# Mega328MLF_Programmer.net
KiCad netlist of a schematic drawn in EAGLE
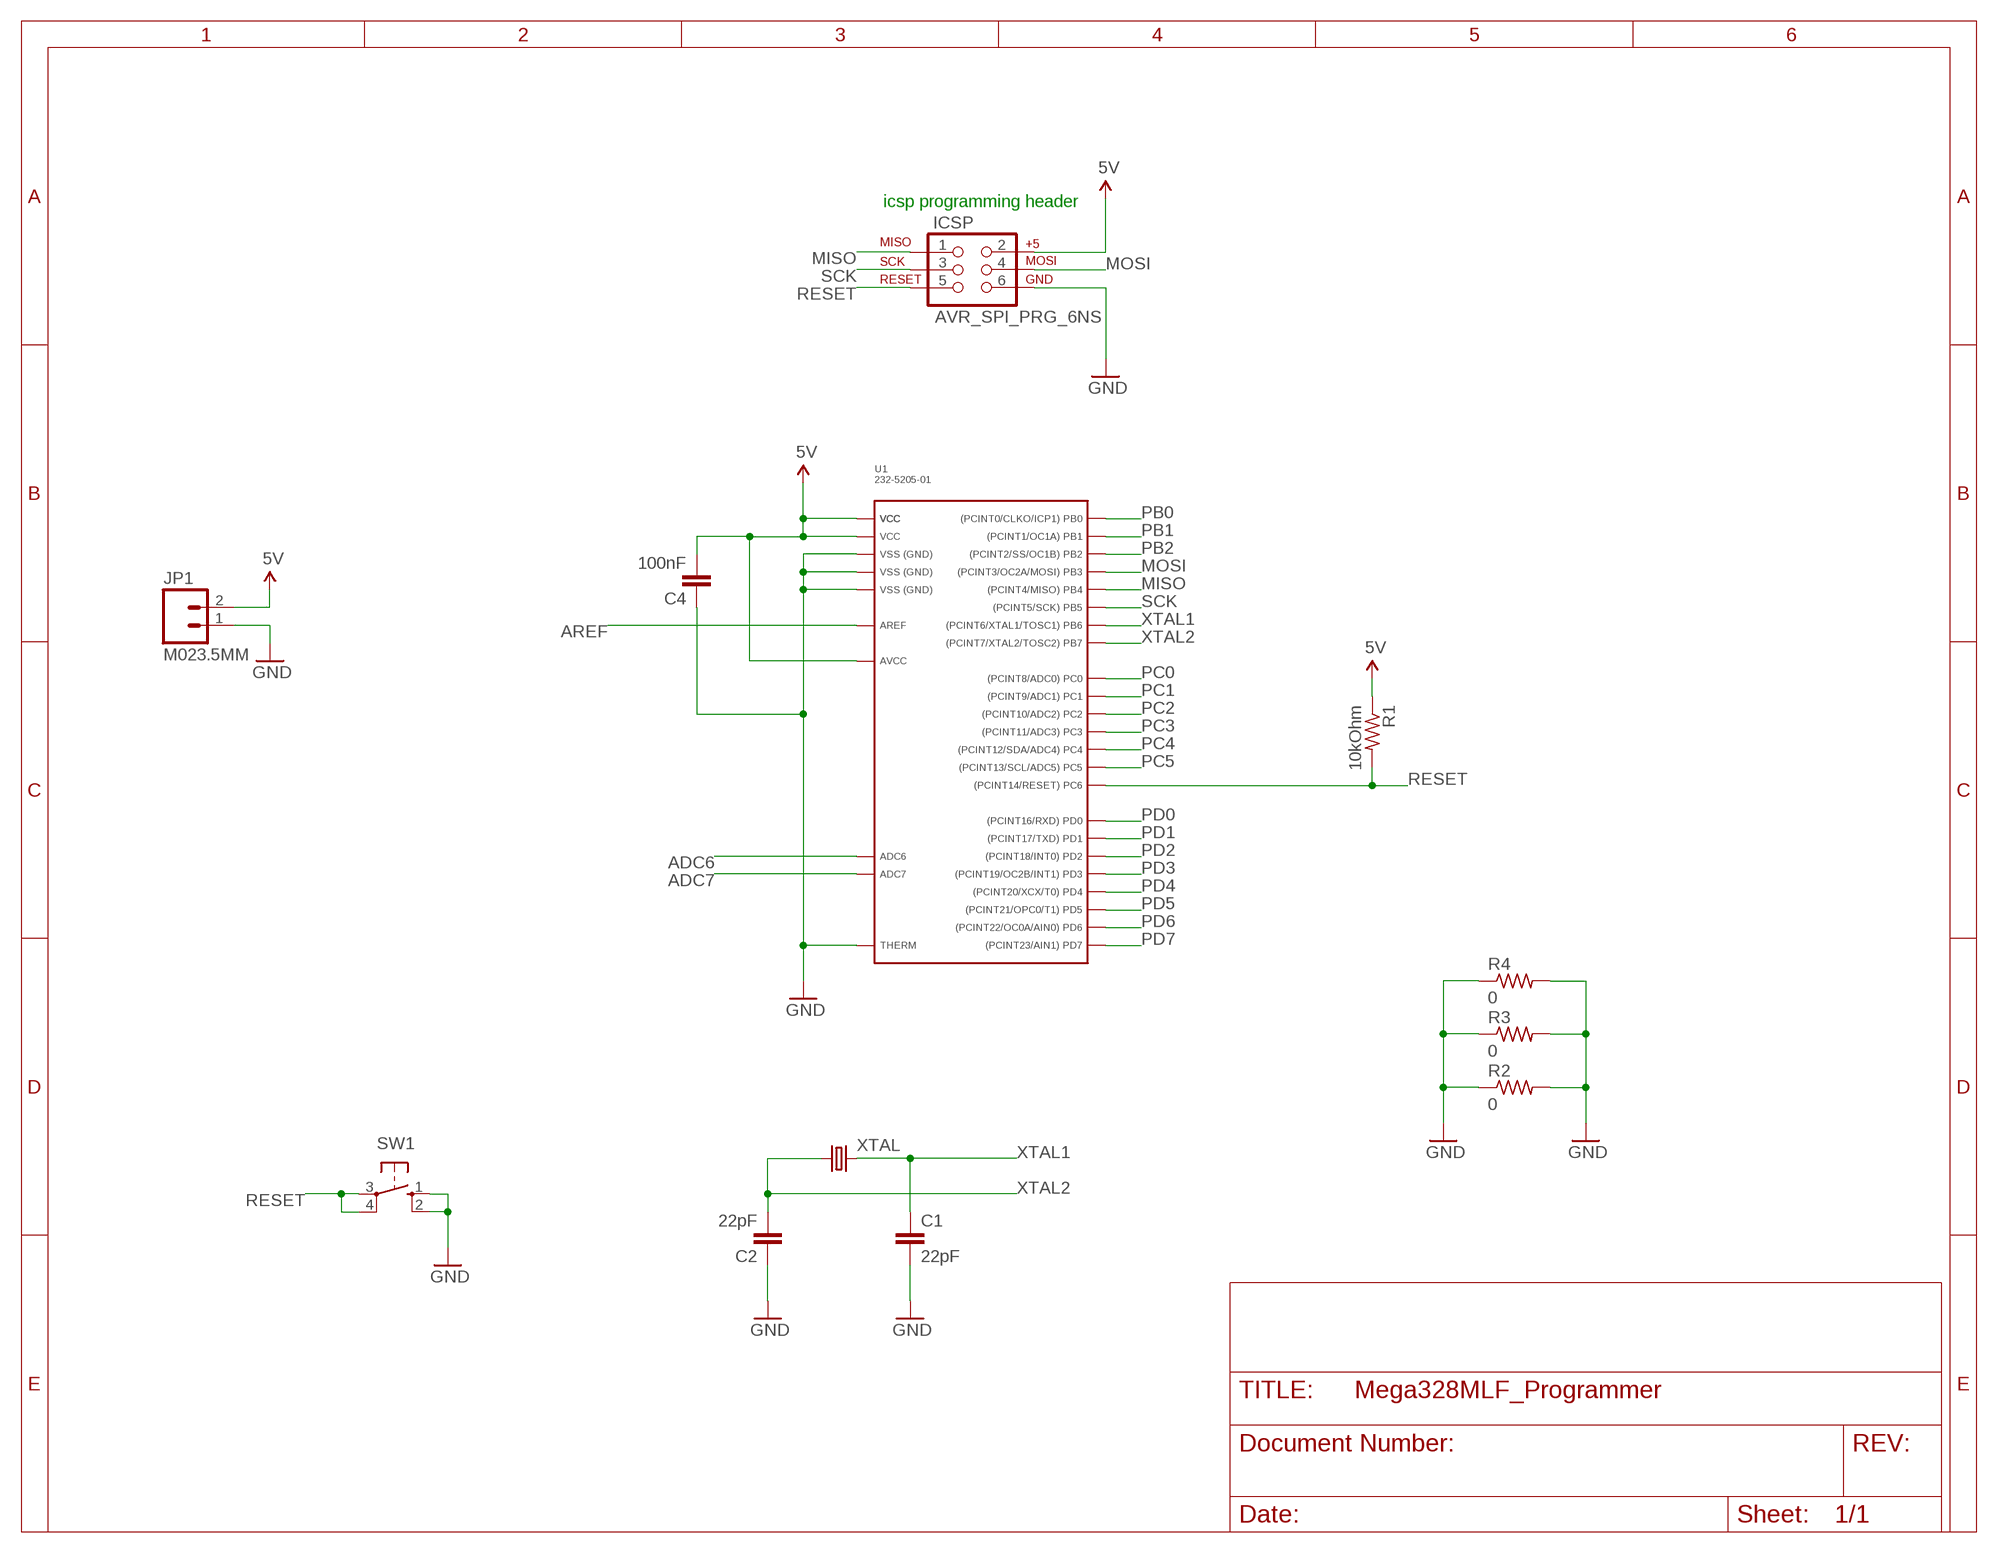
[diagram p0: schematic, sheet 1]

(export (version "E")
  (design (tool "Eeschema 10.0.6"))
  (components
    (comp (ref "C1")
      (value "22pF")
      (footprint "eagle-import:CAP-PTH-SMALL2")
      (libsource (lib "eagle-import") (part "CAPPTH2"))
    )
    (comp (ref "C2")
      (value "22pF")
      (footprint "eagle-import:CAP-PTH-SMALL2")
      (libsource (lib "eagle-import") (part "CAPPTH2"))
    )
    (comp (ref "C4")
      (value "100nF")
      (footprint "eagle-import:CAP-PTH-SMALL2")
      (libsource (lib "eagle-import") (part "CAPPTH2"))
    )
    (comp (ref "ICSP")
      (value "AVR_SPI_PRG_6NS")
      (footprint "eagle-import:2X3-NS")
      (libsource (lib "eagle-import") (part "AVR_SPI_PRG_6NS"))
    )
    (comp (ref "JP1")
      (value "M023.5MM")
      (footprint "eagle-import:SCREWTERMINAL-3.5MM-2")
      (libsource (lib "eagle-import") (part "M023.5MM"))
    )
    (comp (ref "R1")
      (value "10kOhm")
      (footprint "eagle-import:0204_7")
      (libsource (lib "eagle-import") (part "R-US_0204/7"))
    )
    (comp (ref "R2")
      (value "0")
      (footprint "eagle-import:0204_7")
      (libsource (lib "eagle-import") (part "R-US_0204/7"))
    )
    (comp (ref "R3")
      (value "0")
      (footprint "eagle-import:0204_7")
      (libsource (lib "eagle-import") (part "R-US_0204/7"))
    )
    (comp (ref "R4")
      (value "0")
      (footprint "eagle-import:0204_7")
      (libsource (lib "eagle-import") (part "R-US_0204/7"))
    )
    (comp (ref "SW1")
      (value "10-XX")
      (footprint "eagle-import:B3F-10XX")
      (libsource (lib "eagle-import") (part "10-XX"))
    )
    (comp (ref "U1")
      (value "232-5205-01")
      (footprint "eagle-import:232-5205-01")
      (libsource (lib "eagle-import") (part "232-5205-01"))
    )
    (comp (ref "XTAL")
      (value "CRYSTALHC49UV")
      (footprint "eagle-import:HC49U-V")
      (libsource (lib "eagle-import") (part "CRYSTALHC49UV"))
    )
  )
  (nets
    (net (code "1") (name "5V") (class "Default")
      (node (ref "C4") (pin "2") (pinfunction "2_2") (pintype "passive"))
      (node (ref "ICSP") (pin "2") (pinfunction "2_2") (pintype "passive"))
      (node (ref "JP1") (pin "2") (pinfunction "2_2") (pintype "passive"))
      (node (ref "R1") (pin "1") (pinfunction "1_1") (pintype "passive"))
      (node (ref "U1") (pin "18") (pinfunction "AVCC_18") (pintype "power_in"))
      (node (ref "U1") (pin "4") (pinfunction "VCC_4") (pintype "power_in"))
      (node (ref "U1") (pin "6") (pinfunction "VCC_6") (pintype "power_in"))
    )
    (net (code "2") (name "ADC6") (class "Default")
      (node (ref "U1") (pin "19") (pinfunction "ADC6_19") (pintype "bidirectional"))
    )
    (net (code "3") (name "ADC7") (class "Default")
      (node (ref "U1") (pin "22") (pinfunction "ADC7_22") (pintype "bidirectional"))
    )
    (net (code "4") (name "AREF") (class "Default")
      (node (ref "U1") (pin "20") (pinfunction "AREF_20") (pintype "power_in"))
    )
    (net (code "5") (name "GND") (class "Default")
      (node (ref "C1") (pin "2") (pinfunction "2_2") (pintype "passive"))
      (node (ref "C2") (pin "1") (pinfunction "1_1") (pintype "passive"))
      (node (ref "C4") (pin "1") (pinfunction "1_1") (pintype "passive"))
      (node (ref "ICSP") (pin "6") (pinfunction "6_6") (pintype "passive"))
      (node (ref "JP1") (pin "1") (pinfunction "1_1") (pintype "passive"))
      (node (ref "R2") (pin "1") (pinfunction "1_1") (pintype "passive"))
      (node (ref "R2") (pin "2") (pinfunction "2_2") (pintype "passive"))
      (node (ref "R3") (pin "1") (pinfunction "1_1") (pintype "passive"))
      (node (ref "R3") (pin "2") (pinfunction "2_2") (pintype "passive"))
      (node (ref "R4") (pin "1") (pinfunction "1_1") (pintype "passive"))
      (node (ref "R4") (pin "2") (pinfunction "2_2") (pintype "passive"))
      (node (ref "SW1") (pin "1") (pinfunction "S_1") (pintype "passive"))
      (node (ref "SW1") (pin "2") (pinfunction "S1_2") (pintype "passive"))
      (node (ref "U1") (pin "21") (pinfunction "GND_21") (pintype "power_in"))
      (node (ref "U1") (pin "3") (pinfunction "GND_3") (pintype "power_in"))
      (node (ref "U1") (pin "5") (pinfunction "GND_5") (pintype "power_in"))
      (node (ref "U1") (pin "THERM") (pinfunction "THERM_THERM") (pintype "bidirectional"))
    )
    (net (code "6") (name "MISO") (class "Default")
      (node (ref "ICSP") (pin "1") (pinfunction "1_1") (pintype "passive"))
      (node (ref "U1") (pin "16") (pinfunction "PB4_16") (pintype "bidirectional"))
    )
    (net (code "7") (name "MOSI") (class "Default")
      (node (ref "ICSP") (pin "4") (pinfunction "4_4") (pintype "passive"))
      (node (ref "U1") (pin "15") (pinfunction "PB3_15") (pintype "bidirectional"))
    )
    (net (code "8") (name "PB0") (class "Default")
      (node (ref "U1") (pin "12") (pinfunction "PB0_12") (pintype "bidirectional"))
    )
    (net (code "9") (name "PB1") (class "Default")
      (node (ref "U1") (pin "13") (pinfunction "PB1_13") (pintype "bidirectional"))
    )
    (net (code "10") (name "PB2") (class "Default")
      (node (ref "U1") (pin "14") (pinfunction "PB2_14") (pintype "bidirectional"))
    )
    (net (code "11") (name "PC0") (class "Default")
      (node (ref "U1") (pin "23") (pinfunction "PC0_23") (pintype "bidirectional"))
    )
    (net (code "12") (name "PC1") (class "Default")
      (node (ref "U1") (pin "24") (pinfunction "PC1_24") (pintype "bidirectional"))
    )
    (net (code "13") (name "PC2") (class "Default")
      (node (ref "U1") (pin "25") (pinfunction "PC2_25") (pintype "bidirectional"))
    )
    (net (code "14") (name "PC3") (class "Default")
      (node (ref "U1") (pin "26") (pinfunction "PC3_26") (pintype "bidirectional"))
    )
    (net (code "15") (name "PC4") (class "Default")
      (node (ref "U1") (pin "27") (pinfunction "PC4_27") (pintype "bidirectional"))
    )
    (net (code "16") (name "PC5") (class "Default")
      (node (ref "U1") (pin "28") (pinfunction "PC5_28") (pintype "bidirectional"))
    )
    (net (code "17") (name "PD0") (class "Default")
      (node (ref "U1") (pin "30") (pinfunction "PD0_30") (pintype "bidirectional"))
    )
    (net (code "18") (name "PD1") (class "Default")
      (node (ref "U1") (pin "31") (pinfunction "PD1_31") (pintype "bidirectional"))
    )
    (net (code "19") (name "PD2") (class "Default")
      (node (ref "U1") (pin "32") (pinfunction "PD2_32") (pintype "bidirectional"))
    )
    (net (code "20") (name "PD3") (class "Default")
      (node (ref "U1") (pin "1") (pinfunction "PD3_1") (pintype "bidirectional"))
    )
    (net (code "21") (name "PD4") (class "Default")
      (node (ref "U1") (pin "2") (pinfunction "PD4_2") (pintype "bidirectional"))
    )
    (net (code "22") (name "PD5") (class "Default")
      (node (ref "U1") (pin "9") (pinfunction "PD5_9") (pintype "bidirectional"))
    )
    (net (code "23") (name "PD6") (class "Default")
      (node (ref "U1") (pin "10") (pinfunction "PD6_10") (pintype "bidirectional"))
    )
    (net (code "24") (name "PD7") (class "Default")
      (node (ref "U1") (pin "11") (pinfunction "PD7_11") (pintype "bidirectional"))
    )
    (net (code "25") (name "RESET") (class "Default")
      (node (ref "ICSP") (pin "5") (pinfunction "5_5") (pintype "passive"))
      (node (ref "R1") (pin "2") (pinfunction "2_2") (pintype "passive"))
      (node (ref "SW1") (pin "3") (pinfunction "P_3") (pintype "passive"))
      (node (ref "SW1") (pin "4") (pinfunction "P1_4") (pintype "passive"))
      (node (ref "U1") (pin "29") (pinfunction "PC6_29") (pintype "bidirectional"))
    )
    (net (code "26") (name "SCK") (class "Default")
      (node (ref "ICSP") (pin "3") (pinfunction "3_3") (pintype "passive"))
      (node (ref "U1") (pin "17") (pinfunction "PB5_17") (pintype "bidirectional"))
    )
    (net (code "27") (name "XTAL1") (class "Default")
      (node (ref "C1") (pin "1") (pinfunction "1_1") (pintype "passive"))
      (node (ref "U1") (pin "7") (pinfunction "PB6_7") (pintype "bidirectional"))
      (node (ref "XTAL") (pin "2") (pinfunction "2_2") (pintype "passive"))
    )
    (net (code "28") (name "XTAL2") (class "Default")
      (node (ref "C2") (pin "2") (pinfunction "2_2") (pintype "passive"))
      (node (ref "U1") (pin "8") (pinfunction "PB7_8") (pintype "bidirectional"))
      (node (ref "XTAL") (pin "1") (pinfunction "1_1") (pintype "passive"))
    )
  )
)
